# Integrated_LED.net
KiCad netlist of a schematic drawn in Altium Designer
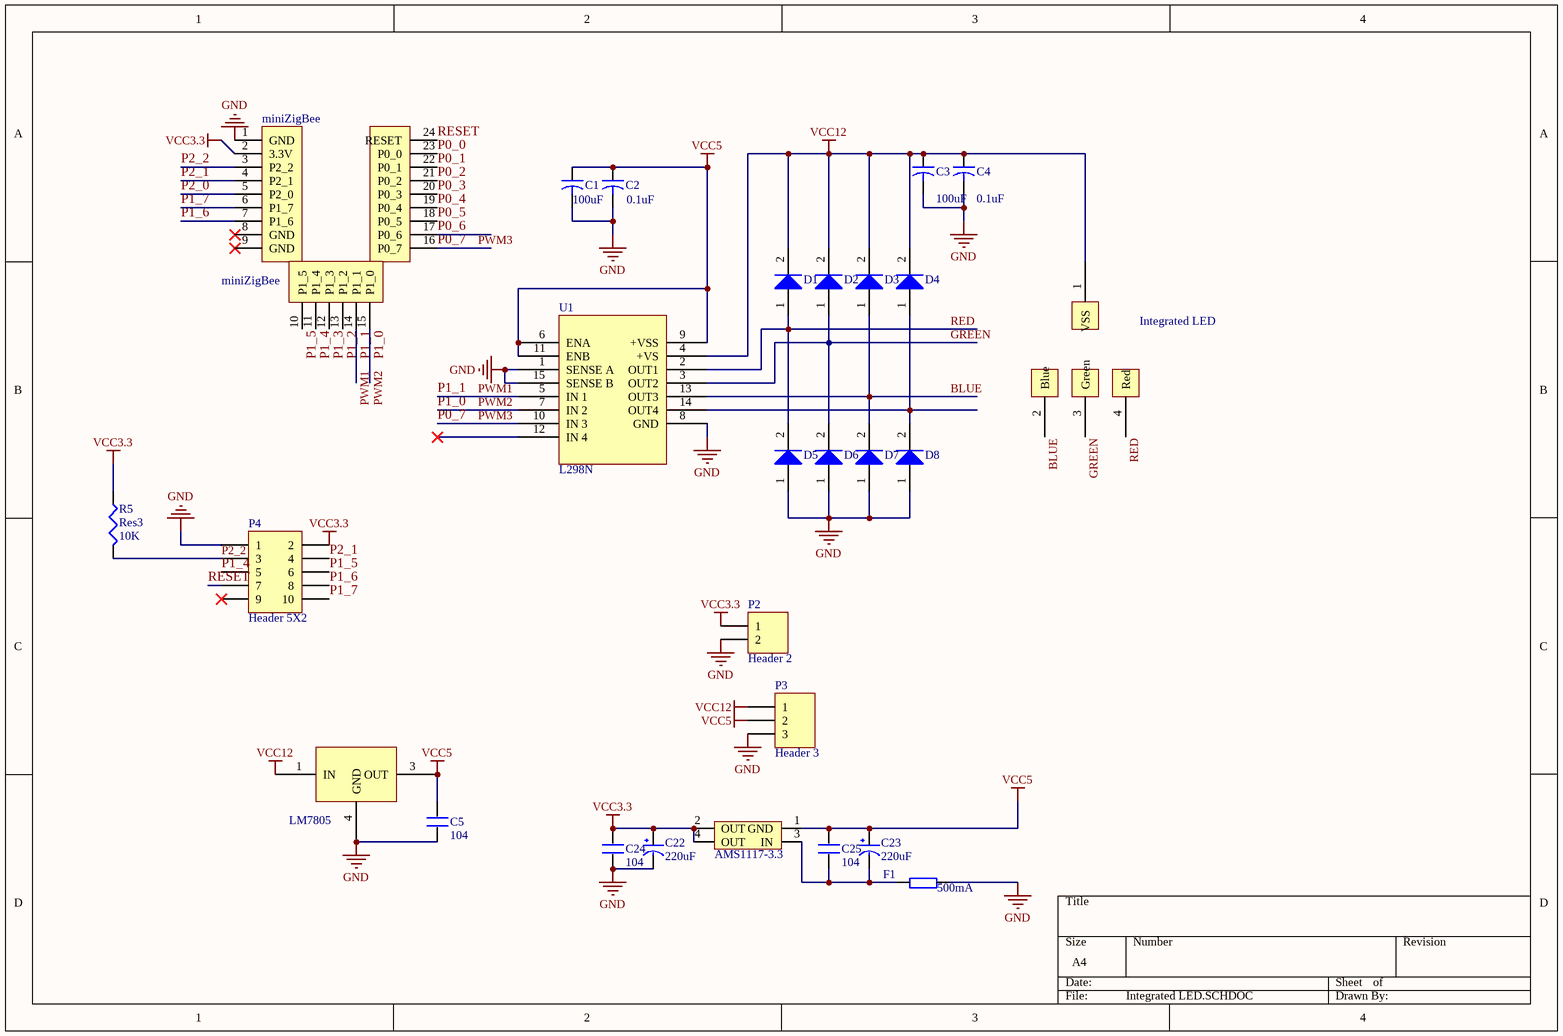
[diagram p0: Integrated LED.SCHDOC]

(export (version "E")
  (design (tool "Eeschema 10.0.6"))
  (components
    (comp (ref "C1")
      (value "100uF")
      (footprint "PCBComponent_1")
      (description "Capacitor")
      (fields (field (name "PUBLISHER") "Altium Limited"))
      (libsource (lib "Miscellaneous Devices") (part "Cap2"))
    )
    (comp (ref "C2")
      (value "0.1uF")
      (footprint "PCBComponent_1")
      (description "Capacitor")
      (fields (field (name "PUBLISHER") "Altium Limited"))
      (libsource (lib "Miscellaneous Devices") (part "Cap2"))
    )
    (comp (ref "C3")
      (value "100uF")
      (footprint "PCBComponent_1")
      (description "Capacitor")
      (fields (field (name "PUBLISHER") "Altium Limited"))
      (libsource (lib "Miscellaneous Devices") (part "Cap2"))
    )
    (comp (ref "C4")
      (value "0.1uF")
      (footprint "PCBComponent_1")
      (description "Capacitor")
      (fields (field (name "PUBLISHER") "Altium Limited"))
      (libsource (lib "Miscellaneous Devices") (part "Cap2"))
    )
    (comp (ref "C5") (value "104") (footprint "0603P") (libsource (lib "my Integrated lib ") (part "C")))
    (comp (ref "C22")
      (value "220uF")
      (footprint "CC6.56.5")
      (libsource (lib "MiniSTM32 V2.0封装库") (part "CAP"))
    )
    (comp (ref "C23")
      (value "220uF")
      (footprint "CC6.56.5")
      (libsource (lib "MiniSTM32 V2.0封装库") (part "CAP"))
    )
    (comp (ref "C24") (value "104") (footprint "0603P") (libsource (lib "MiniSTM32 V2.0封装库") (part "C")))
    (comp (ref "C25") (value "104") (footprint "0603P") (libsource (lib "MiniSTM32 V2.0封装库") (part "C")))
    (comp (ref "D1")
      (value "IN4007")
      (footprint "IN4007")
      (libsource (lib "my Integrated lib ") (part "IN4007"))
    )
    (comp (ref "D2")
      (value "IN4007")
      (footprint "IN4007")
      (libsource (lib "my Integrated lib ") (part "IN4007"))
    )
    (comp (ref "D3")
      (value "IN4007")
      (footprint "IN4007")
      (libsource (lib "my Integrated lib ") (part "IN4007"))
    )
    (comp (ref "D4")
      (value "IN4007")
      (footprint "IN4007")
      (libsource (lib "my Integrated lib ") (part "IN4007"))
    )
    (comp (ref "D5")
      (value "IN4007")
      (footprint "IN4007")
      (libsource (lib "my Integrated lib ") (part "IN4007"))
    )
    (comp (ref "D6")
      (value "IN4007")
      (footprint "IN4007")
      (libsource (lib "my Integrated lib ") (part "IN4007"))
    )
    (comp (ref "D7")
      (value "IN4007")
      (footprint "IN4007")
      (libsource (lib "my Integrated lib ") (part "IN4007"))
    )
    (comp (ref "D8")
      (value "IN4007")
      (footprint "IN4007")
      (libsource (lib "my Integrated lib ") (part "IN4007"))
    )
    (comp (ref "F1") (value "500mA") (footprint "0603P") (libsource (lib "MiniSTM32 V2.0封装库") (part "R")))
    (comp (ref "Integrated LED")
      (value "Integrated LED")
      (footprint "Integrated LED")
      (libsource (lib "my Integrated lib ") (part "Integrated LED"))
    )
    (comp (ref "LM7805")
      (value "LM7805")
      (footprint "LM7805")
      (libsource (lib "my Integrated lib ") (part "LM7805"))
    )
    (comp (ref "miniZigBee")
      (value "miniZigBee")
      (footprint "miniZigBee")
      (libsource (lib "my Integrated lib ") (part "miniZigBee"))
    )
    (comp (ref "P2")
      (value "Header 2")
      (footprint "HDR1X2")
      (description "Header, 2-Pin")
      (fields (field (name "PUBLISHER") "Altium Limited"))
      (libsource (lib "Miscellaneous Connectors") (part "Header 2"))
    )
    (comp (ref "P3")
      (value "Header 3")
      (footprint "HDR1X3")
      (description "Header, 3-Pin")
      (fields (field (name "PUBLISHER") "Altium Limited"))
      (libsource (lib "Miscellaneous Connectors") (part "Header 3"))
    )
    (comp (ref "P4")
      (value "Header 5X2")
      (footprint "HDR2X5")
      (description "Header, 5-Pin, Dual row")
      (fields (field (name "PUBLISHER") "Altium Limited"))
      (libsource (lib "Miscellaneous Connectors") (part "Header 5X2"))
    )
    (comp (ref "R5")
      (value "Res3")
      (footprint "J1-0603")
      (description "Resistor")
      (fields (field (name "ALTIUM_VALUE") "10K") (field (name "PUBLISHER") "Altium Limited"))
      (libsource (lib "Miscellaneous Devices") (part "Res3"))
    )
    (comp (ref "U1") (value "L298N") (footprint "L298N - duplicate") (libsource (lib "KU1") (part "L298N")))
    (comp (ref "U6")
      (value "AMS1117-3.3")
      (footprint "AMS1117")
      (libsource (lib "my Integrated lib ") (part "AMS1117"))
    )
  )
  (nets
    (net (code "1") (name "/BLUE") (class "Default")
      (node (ref "D3") (pin "1") (pinfunction "A_1") (pintype "passive"))
      (node (ref "D7") (pin "2") (pinfunction "K_2") (pintype "passive"))
      (node (ref "Integrated LED") (pin "2") (pinfunction "Blue_2") (pintype "passive"))
      (node (ref "U1") (pin "13") (pinfunction "OUT3_13") (pintype "passive"))
    )
    (net (code "2") (name "/GREEN") (class "Default")
      (node (ref "D2") (pin "1") (pinfunction "A_1") (pintype "passive"))
      (node (ref "D6") (pin "2") (pinfunction "K_2") (pintype "passive"))
      (node (ref "Integrated LED") (pin "3") (pinfunction "Green_3") (pintype "passive"))
      (node (ref "U1") (pin "3") (pinfunction "OUT2_3") (pintype "passive"))
    )
    (net (code "3") (name "/P0_0") (class "Default")
      (node (ref "miniZigBee") (pin "23") (pinfunction "P0_0_23") (pintype "passive"))
    )
    (net (code "4") (name "/P0_1") (class "Default")
      (node (ref "miniZigBee") (pin "22") (pinfunction "P0_1_22") (pintype "passive"))
    )
    (net (code "5") (name "/P0_2") (class "Default")
      (node (ref "miniZigBee") (pin "21") (pinfunction "P0_2_21") (pintype "passive"))
    )
    (net (code "6") (name "/P0_3") (class "Default")
      (node (ref "miniZigBee") (pin "20") (pinfunction "P0_3_20") (pintype "passive"))
    )
    (net (code "7") (name "/P0_4") (class "Default")
      (node (ref "miniZigBee") (pin "19") (pinfunction "P0_4_19") (pintype "passive"))
    )
    (net (code "8") (name "/P0_5") (class "Default")
      (node (ref "miniZigBee") (pin "18") (pinfunction "P0_5_18") (pintype "passive"))
    )
    (net (code "9") (name "/P0_6") (class "Default")
      (node (ref "miniZigBee") (pin "17") (pinfunction "P0_6_17") (pintype "passive"))
    )
    (net (code "10") (name "/P0_7") (class "Default")
      (node (ref "U1") (pin "10") (pinfunction "IN_3_10") (pintype "passive"))
      (node (ref "miniZigBee") (pin "16") (pinfunction "P0_7_16") (pintype "passive"))
    )
    (net (code "11") (name "/P1_0") (class "Default")
      (node (ref "U1") (pin "7") (pinfunction "IN_2_7") (pintype "passive"))
      (node (ref "miniZigBee") (pin "15") (pinfunction "P1_0_15") (pintype "passive"))
    )
    (net (code "12") (name "/P1_1") (class "Default")
      (node (ref "U1") (pin "5") (pinfunction "IN_1_5") (pintype "passive"))
      (node (ref "miniZigBee") (pin "14") (pinfunction "P1_1_14") (pintype "passive"))
    )
    (net (code "13") (name "/P1_2") (class "Default")
      (node (ref "miniZigBee") (pin "13") (pinfunction "P1_2_13") (pintype "passive"))
    )
    (net (code "14") (name "/P1_3") (class "Default")
      (node (ref "miniZigBee") (pin "12") (pinfunction "P1_3_12") (pintype "passive"))
    )
    (net (code "15") (name "/P1_4") (class "Default")
      (node (ref "P4") (pin "5") (pinfunction "5_5") (pintype "passive"))
      (node (ref "miniZigBee") (pin "11") (pinfunction "P1_4_11") (pintype "passive"))
    )
    (net (code "16") (name "/P1_5") (class "Default")
      (node (ref "P4") (pin "6") (pinfunction "6_6") (pintype "passive"))
      (node (ref "miniZigBee") (pin "10") (pinfunction "P1_5_10") (pintype "passive"))
    )
    (net (code "17") (name "/P1_6") (class "Default")
      (node (ref "P4") (pin "8") (pinfunction "8_8") (pintype "passive"))
      (node (ref "miniZigBee") (pin "7") (pinfunction "P1_6_7") (pintype "passive"))
    )
    (net (code "18") (name "/P1_7") (class "Default")
      (node (ref "P4") (pin "10") (pinfunction "10_10") (pintype "passive"))
      (node (ref "miniZigBee") (pin "6") (pinfunction "P1_7_6") (pintype "passive"))
    )
    (net (code "19") (name "/P2_0") (class "Default")
      (node (ref "miniZigBee") (pin "5") (pinfunction "P2_0_5") (pintype "passive"))
    )
    (net (code "20") (name "/P2_1") (class "Default")
      (node (ref "P4") (pin "4") (pinfunction "4_4") (pintype "passive"))
      (node (ref "miniZigBee") (pin "4") (pinfunction "P2_1_4") (pintype "passive"))
    )
    (net (code "21") (name "/P2_2") (class "Default")
      (node (ref "P4") (pin "3") (pinfunction "3_3") (pintype "passive"))
      (node (ref "R5") (pin "2") (pinfunction "2_2") (pintype "passive"))
      (node (ref "miniZigBee") (pin "3") (pinfunction "P2_2_3") (pintype "passive"))
    )
    (net (code "22") (name "/RED") (class "Default")
      (node (ref "D1") (pin "1") (pinfunction "A_1") (pintype "passive"))
      (node (ref "D5") (pin "2") (pinfunction "K_2") (pintype "passive"))
      (node (ref "Integrated LED") (pin "4") (pinfunction "Red_4") (pintype "passive"))
      (node (ref "U1") (pin "2") (pinfunction "OUT1_2") (pintype "passive"))
    )
    (net (code "23") (name "/RESET") (class "Default")
      (node (ref "P4") (pin "7") (pinfunction "7_7") (pintype "passive"))
      (node (ref "miniZigBee") (pin "24") (pinfunction "RESET_24") (pintype "passive"))
    )
    (net (code "24") (name "GND") (class "Default")
      (node (ref "C1") (pin "2") (pinfunction "2_2") (pintype "passive"))
      (node (ref "C2") (pin "2") (pinfunction "2_2") (pintype "passive"))
      (node (ref "C22") (pin "2") (pinfunction "GND_2") (pintype "passive"))
      (node (ref "C24") (pin "1") (pintype "passive"))
      (node (ref "C3") (pin "2") (pinfunction "2_2") (pintype "passive"))
      (node (ref "C4") (pin "2") (pinfunction "2_2") (pintype "passive"))
      (node (ref "C5") (pin "1") (pintype "passive"))
      (node (ref "D5") (pin "1") (pinfunction "A_1") (pintype "passive"))
      (node (ref "D6") (pin "1") (pinfunction "A_1") (pintype "passive"))
      (node (ref "D7") (pin "1") (pinfunction "A_1") (pintype "passive"))
      (node (ref "D8") (pin "1") (pinfunction "A_1") (pintype "passive"))
      (node (ref "F1") (pin "2") (pintype "passive"))
      (node (ref "LM7805") (pin "4") (pinfunction "GND_4") (pintype "passive"))
      (node (ref "P2") (pin "2") (pinfunction "2_2") (pintype "passive"))
      (node (ref "P3") (pin "3") (pinfunction "3_3") (pintype "passive"))
      (node (ref "P4") (pin "1") (pinfunction "1_1") (pintype "passive"))
      (node (ref "U1") (pin "1") (pinfunction "SENSE_A_1") (pintype "passive"))
      (node (ref "U1") (pin "15") (pinfunction "SENSE_B_15") (pintype "passive"))
      (node (ref "U1") (pin "8") (pinfunction "GND_8") (pintype "passive"))
      (node (ref "miniZigBee") (pin "1") (pinfunction "GND_1") (pintype "passive"))
    )
    (net (code "25") (name "Net-(C23-GND)") (class "Default")
      (node (ref "C23") (pin "2") (pinfunction "GND_2") (pintype "passive"))
      (node (ref "C25") (pin "1") (pintype "passive"))
      (node (ref "F1") (pin "1") (pintype "passive"))
      (node (ref "U6") (pin "3") (pinfunction "IN_3") (pintype "passive"))
    )
    (net (code "26") (name "Net-(D4-A)") (class "Default")
      (node (ref "D4") (pin "1") (pinfunction "A_1") (pintype "passive"))
      (node (ref "D8") (pin "2") (pinfunction "K_2") (pintype "passive"))
      (node (ref "U1") (pin "14") (pinfunction "OUT4_14") (pintype "passive"))
    )
    (net (code "27") (name "VCC3.3") (class "Default")
      (node (ref "C22") (pin "1") (pinfunction "VCC_1") (pintype "passive"))
      (node (ref "C24") (pin "2") (pintype "passive"))
      (node (ref "P2") (pin "1") (pinfunction "1_1") (pintype "passive"))
      (node (ref "P4") (pin "2") (pinfunction "2_2") (pintype "passive"))
      (node (ref "R5") (pin "1") (pinfunction "1_1") (pintype "passive"))
      (node (ref "U6") (pin "2") (pinfunction "OUT_2") (pintype "passive"))
      (node (ref "U6") (pin "4") (pinfunction "OUT_4") (pintype "passive"))
      (node (ref "miniZigBee") (pin "2") (pinfunction "3.3V_2") (pintype "passive"))
    )
    (net (code "28") (name "VCC5") (class "Default")
      (node (ref "C1") (pin "1") (pinfunction "1_1") (pintype "passive"))
      (node (ref "C2") (pin "1") (pinfunction "1_1") (pintype "passive"))
      (node (ref "C23") (pin "1") (pinfunction "VCC_1") (pintype "passive"))
      (node (ref "C25") (pin "2") (pintype "passive"))
      (node (ref "C5") (pin "2") (pintype "passive"))
      (node (ref "LM7805") (pin "3") (pinfunction "OUT_3") (pintype "passive"))
      (node (ref "P3") (pin "2") (pinfunction "2_2") (pintype "passive"))
      (node (ref "U1") (pin "11") (pinfunction "ENB_11") (pintype "passive"))
      (node (ref "U1") (pin "6") (pinfunction "ENA_6") (pintype "passive"))
      (node (ref "U1") (pin "9") (pinfunction "+VSS_9") (pintype "passive"))
      (node (ref "U6") (pin "1") (pinfunction "GND_1") (pintype "passive"))
    )
    (net (code "29") (name "VCC12") (class "Default")
      (node (ref "C3") (pin "1") (pinfunction "1_1") (pintype "passive"))
      (node (ref "C4") (pin "1") (pinfunction "1_1") (pintype "passive"))
      (node (ref "D1") (pin "2") (pinfunction "K_2") (pintype "passive"))
      (node (ref "D2") (pin "2") (pinfunction "K_2") (pintype "passive"))
      (node (ref "D3") (pin "2") (pinfunction "K_2") (pintype "passive"))
      (node (ref "D4") (pin "2") (pinfunction "K_2") (pintype "passive"))
      (node (ref "Integrated LED") (pin "1") (pinfunction "VSS_1") (pintype "passive"))
      (node (ref "LM7805") (pin "1") (pinfunction "IN_1") (pintype "passive"))
      (node (ref "P3") (pin "1") (pinfunction "1_1") (pintype "passive"))
      (node (ref "U1") (pin "4") (pinfunction "+VS_4") (pintype "passive"))
    )
    (net (code "30") (name "unconnected-(P4-Pad9)") (class "Default")
      (node (ref "P4") (pin "9") (pinfunction "9_9") (pintype "passive+no_connect"))
    )
    (net (code "31") (name "unconnected-(U1-IN_4-Pad12)") (class "Default")
      (node (ref "U1") (pin "12") (pinfunction "IN_4_12") (pintype "passive+no_connect"))
    )
    (net (code "32") (name "unconnected-(miniZigBee-GND-Pad8)") (class "Default")
      (node (ref "miniZigBee") (pin "8") (pinfunction "GND_8") (pintype "passive+no_connect"))
    )
    (net (code "33") (name "unconnected-(miniZigBee-GND-Pad9)") (class "Default")
      (node (ref "miniZigBee") (pin "9") (pinfunction "GND_9") (pintype "passive+no_connect"))
    )
  )
)
